# FPGA_I2C.net
KiCad netlist of a schematic drawn in Altium Designer
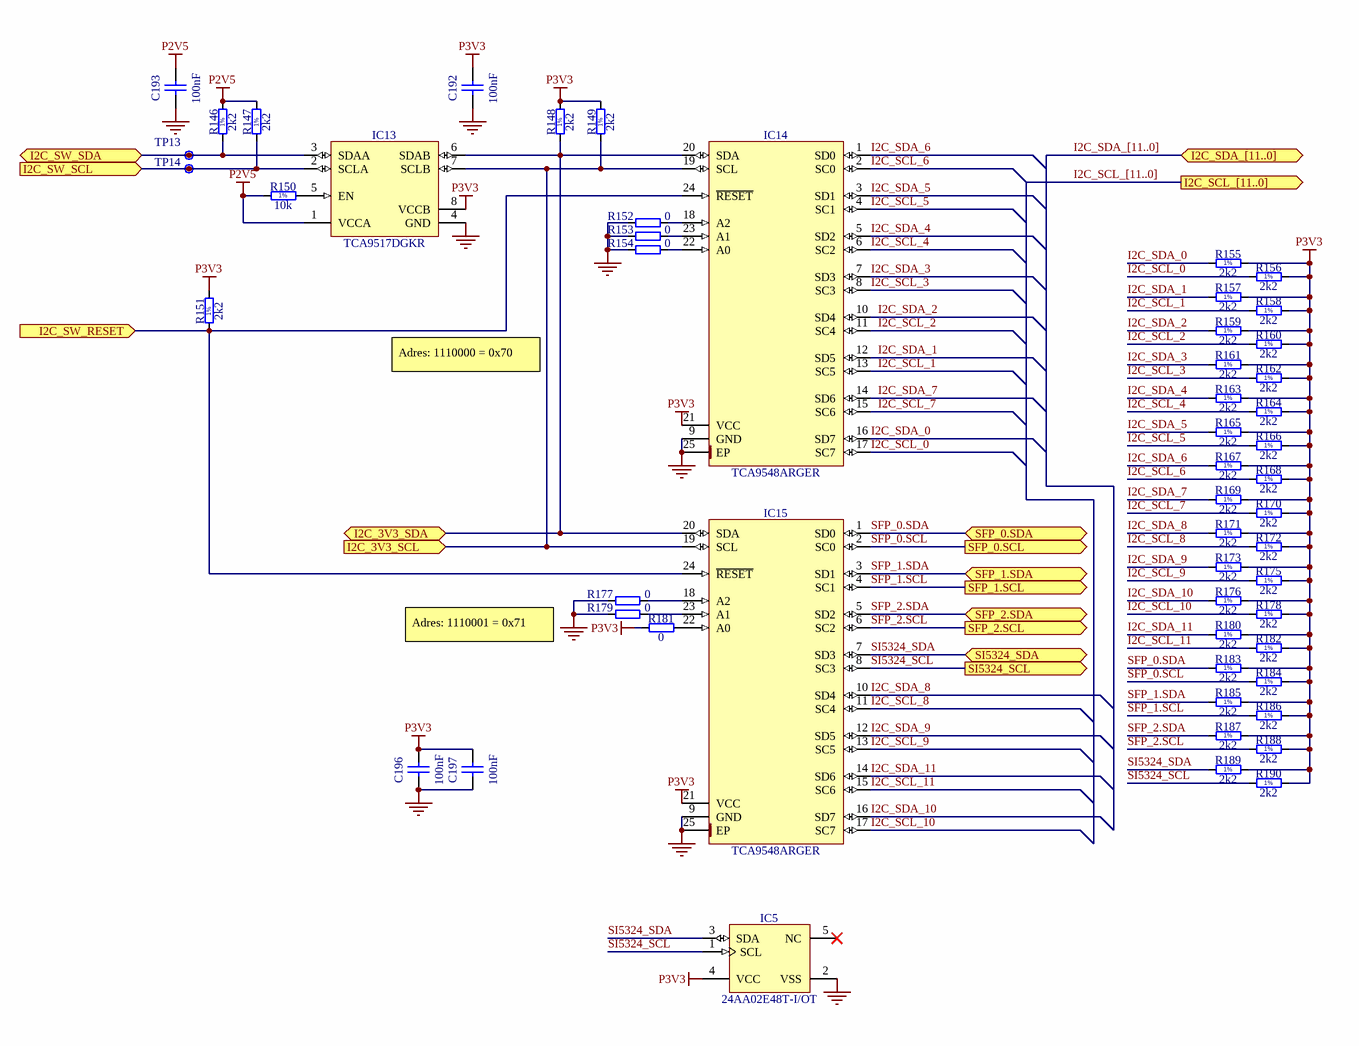
[diagram p0: FPGA_I2C.SchDoc]

(export (version "E")
  (design (tool "Eeschema 10.0.6"))
  (components
    (comp (ref "C192")
      (value "100nF")
      (footprint "CAPC0603X33N")
      (description "Non-polarised capacitor")
      (fields
        (field (name "PART NUMBER") "CC0201_100NF_6.3V_10%_X5R")
        (field (name "VOLTAGE") "6.3V")
        (field (name "AUTHOR") "CERN DEM JLC")
      )
      (libsource (lib "Capacitors") (part "Capacitor - non polarized"))
    )
    (comp (ref "C193")
      (value "100nF")
      (footprint "CAPC0603X33N")
      (description "Non-polarised capacitor")
      (fields
        (field (name "PART NUMBER") "CC0201_100NF_6.3V_10%_X5R")
        (field (name "VOLTAGE") "6.3V")
        (field (name "AUTHOR") "CERN DEM JLC")
      )
      (libsource (lib "Capacitors") (part "Capacitor - non polarized"))
    )
    (comp (ref "C196")
      (value "100nF")
      (footprint "CAPC0603X33N")
      (description "Non-polarised capacitor")
      (fields
        (field (name "PART NUMBER") "CC0201_100NF_6.3V_10%_X5R")
        (field (name "VOLTAGE") "6.3V")
        (field (name "AUTHOR") "CERN DEM JLC")
      )
      (libsource (lib "Capacitors") (part "Capacitor - non polarized"))
    )
    (comp (ref "C197")
      (value "100nF")
      (footprint "CAPC0603X33N")
      (description "Non-polarised capacitor")
      (fields
        (field (name "PART NUMBER") "CC0201_100NF_6.3V_10%_X5R")
        (field (name "VOLTAGE") "6.3V")
        (field (name "AUTHOR") "CERN DEM JLC")
      )
      (libsource (lib "Capacitors") (part "Capacitor - non polarized"))
    )
    (comp (ref "IC5")
      (value "24AA02E48T-I/OT")
      (footprint "SOT95P280X145-5N")
      (description "1.7V-5.5V, 2K I2C Serial EEPROM With EUI-48 Node Identity")
      (fields (field (name "MANUFACTURER") "MICROCHIP TECHNOLOGY") (field (name "AUTHOR") "CERN DEM MR"))
      (libsource (lib "ICs And Semiconductors") (part "24AA02E48T-I/OT"))
    )
    (comp (ref "IC13")
      (value "TCA9517DGKR")
      (footprint "SOP65P490X110-8N")
      (description "Level-Translating I2C Bus Repeater")
      (fields (field (name "MANUFACTURER") "TEXAS INSTRUMENTS") (field (name "AUTHOR") "CERN DEM JLC"))
      (libsource (lib "ICs And Semiconductors") (part "TCA9517"))
    )
    (comp (ref "IC14")
      (value "TCA9548ARGER")
      (footprint "QFN50P400X400X100-25N-S220")
      (description "Low Voltage 8-Channel I2C Switch With Reset")
      (fields (field (name "MANUFACTURER") "TEXAS INSTRUMENTS") (field (name "AUTHOR") "CERN DEM JLC"))
      (libsource (lib "ICs And Semiconductors") (part "TCA9548ARGER"))
    )
    (comp (ref "IC15")
      (value "TCA9548ARGER")
      (footprint "QFN50P400X400X100-25N-S220")
      (description "Low Voltage 8-Channel I2C Switch With Reset")
      (fields (field (name "MANUFACTURER") "TEXAS INSTRUMENTS") (field (name "AUTHOR") "CERN DEM JLC"))
      (libsource (lib "ICs And Semiconductors") (part "TCA9548ARGER"))
    )
    (comp (ref "R146")
      (value "2k2")
      (footprint "RESC1005X40N")
      (description "Resistor - 1%")
      (fields
        (field (name "PART NUMBER") "R0402_2K2_1%_0.0625W_100PPM")
        (field (name "POWER") "0.0625W")
        (field (name "AUTHOR") "CERN DEM JLC")
      )
      (libsource (lib "Resistors") (part "Resistor - 1%"))
    )
    (comp (ref "R147")
      (value "2k2")
      (footprint "RESC1005X40N")
      (description "Resistor - 1%")
      (fields
        (field (name "PART NUMBER") "R0402_2K2_1%_0.0625W_100PPM")
        (field (name "POWER") "0.0625W")
        (field (name "AUTHOR") "CERN DEM JLC")
      )
      (libsource (lib "Resistors") (part "Resistor - 1%"))
    )
    (comp (ref "R148")
      (value "2k2")
      (footprint "RESC1005X40N")
      (description "Resistor - 1%")
      (fields
        (field (name "PART NUMBER") "R0402_2K2_1%_0.0625W_100PPM")
        (field (name "POWER") "0.0625W")
        (field (name "AUTHOR") "CERN DEM JLC")
      )
      (libsource (lib "Resistors") (part "Resistor - 1%"))
    )
    (comp (ref "R149")
      (value "2k2")
      (footprint "RESC1005X40N")
      (description "Resistor - 1%")
      (fields
        (field (name "PART NUMBER") "R0402_2K2_1%_0.0625W_100PPM")
        (field (name "POWER") "0.0625W")
        (field (name "AUTHOR") "CERN DEM JLC")
      )
      (libsource (lib "Resistors") (part "Resistor - 1%"))
    )
    (comp (ref "R150")
      (value "10k")
      (footprint "RESC1005X40N")
      (description "Resistor - 1%")
      (fields
        (field (name "PART NUMBER") "R0402_10K_1%_0.0625W_100PPM")
        (field (name "POWER") "0.0625W")
        (field (name "AUTHOR") "CERN DEM JLC")
      )
      (libsource (lib "Resistors") (part "Resistor - 1%"))
    )
    (comp (ref "R151")
      (value "2k2")
      (footprint "RESC1005X40N")
      (description "Resistor - 1%")
      (fields
        (field (name "PART NUMBER") "R0402_2K2_1%_0.0625W_100PPM")
        (field (name "POWER") "0.0625W")
        (field (name "AUTHOR") "CERN DEM JLC")
      )
      (libsource (lib "Resistors") (part "Resistor - 1%"))
    )
    (comp (ref "R152")
      (value "0")
      (footprint "RESC1005X40N")
      (description "Resistor")
      (fields
        (field (name "PART NUMBER") "R0402_0R_JUMPER")
        (field (name "MANUFACTURER") "GENERIC")
        (field (name "AUTHOR") "CERN DEM JLC")
      )
      (libsource (lib "Resistors") (part "Resistor"))
    )
    (comp (ref "R153")
      (value "0")
      (footprint "RESC1005X40N")
      (description "Resistor")
      (fields
        (field (name "PART NUMBER") "R0402_0R_JUMPER")
        (field (name "MANUFACTURER") "GENERIC")
        (field (name "AUTHOR") "CERN DEM JLC")
      )
      (libsource (lib "Resistors") (part "Resistor"))
    )
    (comp (ref "R154")
      (value "0")
      (footprint "RESC1005X40N")
      (description "Resistor")
      (fields
        (field (name "PART NUMBER") "R0402_0R_JUMPER")
        (field (name "MANUFACTURER") "GENERIC")
        (field (name "AUTHOR") "CERN DEM JLC")
      )
      (libsource (lib "Resistors") (part "Resistor"))
    )
    (comp (ref "R155")
      (value "2k2")
      (footprint "RESC1005X40N")
      (description "Resistor - 1%")
      (fields
        (field (name "PART NUMBER") "R0402_2K2_1%_0.0625W_100PPM")
        (field (name "POWER") "0.0625W")
        (field (name "AUTHOR") "CERN DEM JLC")
      )
      (libsource (lib "Resistors") (part "Resistor - 1%"))
    )
    (comp (ref "R156")
      (value "2k2")
      (footprint "RESC1005X40N")
      (description "Resistor - 1%")
      (fields
        (field (name "PART NUMBER") "R0402_2K2_1%_0.0625W_100PPM")
        (field (name "POWER") "0.0625W")
        (field (name "AUTHOR") "CERN DEM JLC")
      )
      (libsource (lib "Resistors") (part "Resistor - 1%"))
    )
    (comp (ref "R157")
      (value "2k2")
      (footprint "RESC1005X40N")
      (description "Resistor - 1%")
      (fields
        (field (name "PART NUMBER") "R0402_2K2_1%_0.0625W_100PPM")
        (field (name "POWER") "0.0625W")
        (field (name "AUTHOR") "CERN DEM JLC")
      )
      (libsource (lib "Resistors") (part "Resistor - 1%"))
    )
    (comp (ref "R158")
      (value "2k2")
      (footprint "RESC1005X40N")
      (description "Resistor - 1%")
      (fields
        (field (name "PART NUMBER") "R0402_2K2_1%_0.0625W_100PPM")
        (field (name "POWER") "0.0625W")
        (field (name "AUTHOR") "CERN DEM JLC")
      )
      (libsource (lib "Resistors") (part "Resistor - 1%"))
    )
    (comp (ref "R159")
      (value "2k2")
      (footprint "RESC1005X40N")
      (description "Resistor - 1%")
      (fields
        (field (name "PART NUMBER") "R0402_2K2_1%_0.0625W_100PPM")
        (field (name "POWER") "0.0625W")
        (field (name "AUTHOR") "CERN DEM JLC")
      )
      (libsource (lib "Resistors") (part "Resistor - 1%"))
    )
    (comp (ref "R160")
      (value "2k2")
      (footprint "RESC1005X40N")
      (description "Resistor - 1%")
      (fields
        (field (name "PART NUMBER") "R0402_2K2_1%_0.0625W_100PPM")
        (field (name "POWER") "0.0625W")
        (field (name "AUTHOR") "CERN DEM JLC")
      )
      (libsource (lib "Resistors") (part "Resistor - 1%"))
    )
    (comp (ref "R161")
      (value "2k2")
      (footprint "RESC1005X40N")
      (description "Resistor - 1%")
      (fields
        (field (name "PART NUMBER") "R0402_2K2_1%_0.0625W_100PPM")
        (field (name "POWER") "0.0625W")
        (field (name "AUTHOR") "CERN DEM JLC")
      )
      (libsource (lib "Resistors") (part "Resistor - 1%"))
    )
    (comp (ref "R162")
      (value "2k2")
      (footprint "RESC1005X40N")
      (description "Resistor - 1%")
      (fields
        (field (name "PART NUMBER") "R0402_2K2_1%_0.0625W_100PPM")
        (field (name "POWER") "0.0625W")
        (field (name "AUTHOR") "CERN DEM JLC")
      )
      (libsource (lib "Resistors") (part "Resistor - 1%"))
    )
    (comp (ref "R163")
      (value "2k2")
      (footprint "RESC1005X40N")
      (description "Resistor - 1%")
      (fields
        (field (name "PART NUMBER") "R0402_2K2_1%_0.0625W_100PPM")
        (field (name "POWER") "0.0625W")
        (field (name "AUTHOR") "CERN DEM JLC")
      )
      (libsource (lib "Resistors") (part "Resistor - 1%"))
    )
    (comp (ref "R164")
      (value "2k2")
      (footprint "RESC1005X40N")
      (description "Resistor - 1%")
      (fields
        (field (name "PART NUMBER") "R0402_2K2_1%_0.0625W_100PPM")
        (field (name "POWER") "0.0625W")
        (field (name "AUTHOR") "CERN DEM JLC")
      )
      (libsource (lib "Resistors") (part "Resistor - 1%"))
    )
    (comp (ref "R165")
      (value "2k2")
      (footprint "RESC1005X40N")
      (description "Resistor - 1%")
      (fields
        (field (name "PART NUMBER") "R0402_2K2_1%_0.0625W_100PPM")
        (field (name "POWER") "0.0625W")
        (field (name "AUTHOR") "CERN DEM JLC")
      )
      (libsource (lib "Resistors") (part "Resistor - 1%"))
    )
    (comp (ref "R166")
      (value "2k2")
      (footprint "RESC1005X40N")
      (description "Resistor - 1%")
      (fields
        (field (name "PART NUMBER") "R0402_2K2_1%_0.0625W_100PPM")
        (field (name "POWER") "0.0625W")
        (field (name "AUTHOR") "CERN DEM JLC")
      )
      (libsource (lib "Resistors") (part "Resistor - 1%"))
    )
    (comp (ref "R167")
      (value "2k2")
      (footprint "RESC1005X40N")
      (description "Resistor - 1%")
      (fields
        (field (name "PART NUMBER") "R0402_2K2_1%_0.0625W_100PPM")
        (field (name "POWER") "0.0625W")
        (field (name "AUTHOR") "CERN DEM JLC")
      )
      (libsource (lib "Resistors") (part "Resistor - 1%"))
    )
    (comp (ref "R168")
      (value "2k2")
      (footprint "RESC1005X40N")
      (description "Resistor - 1%")
      (fields
        (field (name "PART NUMBER") "R0402_2K2_1%_0.0625W_100PPM")
        (field (name "POWER") "0.0625W")
        (field (name "AUTHOR") "CERN DEM JLC")
      )
      (libsource (lib "Resistors") (part "Resistor - 1%"))
    )
    (comp (ref "R169")
      (value "2k2")
      (footprint "RESC1005X40N")
      (description "Resistor - 1%")
      (fields
        (field (name "PART NUMBER") "R0402_2K2_1%_0.0625W_100PPM")
        (field (name "POWER") "0.0625W")
        (field (name "AUTHOR") "CERN DEM JLC")
      )
      (libsource (lib "Resistors") (part "Resistor - 1%"))
    )
    (comp (ref "R170")
      (value "2k2")
      (footprint "RESC1005X40N")
      (description "Resistor - 1%")
      (fields
        (field (name "PART NUMBER") "R0402_2K2_1%_0.0625W_100PPM")
        (field (name "POWER") "0.0625W")
        (field (name "AUTHOR") "CERN DEM JLC")
      )
      (libsource (lib "Resistors") (part "Resistor - 1%"))
    )
    (comp (ref "R171")
      (value "2k2")
      (footprint "RESC1005X40N")
      (description "Resistor - 1%")
      (fields
        (field (name "PART NUMBER") "R0402_2K2_1%_0.0625W_100PPM")
        (field (name "POWER") "0.0625W")
        (field (name "AUTHOR") "CERN DEM JLC")
      )
      (libsource (lib "Resistors") (part "Resistor - 1%"))
    )
    (comp (ref "R172")
      (value "2k2")
      (footprint "RESC1005X40N")
      (description "Resistor - 1%")
      (fields
        (field (name "PART NUMBER") "R0402_2K2_1%_0.0625W_100PPM")
        (field (name "POWER") "0.0625W")
        (field (name "AUTHOR") "CERN DEM JLC")
      )
      (libsource (lib "Resistors") (part "Resistor - 1%"))
    )
    (comp (ref "R173")
      (value "2k2")
      (footprint "RESC1005X40N")
      (description "Resistor - 1%")
      (fields
        (field (name "PART NUMBER") "R0402_2K2_1%_0.0625W_100PPM")
        (field (name "POWER") "0.0625W")
        (field (name "AUTHOR") "CERN DEM JLC")
      )
      (libsource (lib "Resistors") (part "Resistor - 1%"))
    )
    (comp (ref "R175")
      (value "2k2")
      (footprint "RESC1005X40N")
      (description "Resistor - 1%")
      (fields
        (field (name "PART NUMBER") "R0402_2K2_1%_0.0625W_100PPM")
        (field (name "POWER") "0.0625W")
        (field (name "AUTHOR") "CERN DEM JLC")
      )
      (libsource (lib "Resistors") (part "Resistor - 1%"))
    )
    (comp (ref "R176")
      (value "2k2")
      (footprint "RESC1005X40N")
      (description "Resistor - 1%")
      (fields
        (field (name "PART NUMBER") "R0402_2K2_1%_0.0625W_100PPM")
        (field (name "POWER") "0.0625W")
        (field (name "AUTHOR") "CERN DEM JLC")
      )
      (libsource (lib "Resistors") (part "Resistor - 1%"))
    )
    (comp (ref "R177")
      (value "0")
      (footprint "RESC1005X40N")
      (description "Resistor")
      (fields
        (field (name "PART NUMBER") "R0402_0R_JUMPER")
        (field (name "MANUFACTURER") "GENERIC")
        (field (name "AUTHOR") "CERN DEM JLC")
      )
      (libsource (lib "Resistors") (part "Resistor"))
    )
    (comp (ref "R178")
      (value "2k2")
      (footprint "RESC1005X40N")
      (description "Resistor - 1%")
      (fields
        (field (name "PART NUMBER") "R0402_2K2_1%_0.0625W_100PPM")
        (field (name "POWER") "0.0625W")
        (field (name "AUTHOR") "CERN DEM JLC")
      )
      (libsource (lib "Resistors") (part "Resistor - 1%"))
    )
    (comp (ref "R179")
      (value "0")
      (footprint "RESC1005X40N")
      (description "Resistor")
      (fields
        (field (name "PART NUMBER") "R0402_0R_JUMPER")
        (field (name "MANUFACTURER") "GENERIC")
        (field (name "AUTHOR") "CERN DEM JLC")
      )
      (libsource (lib "Resistors") (part "Resistor"))
    )
    (comp (ref "R180")
      (value "2k2")
      (footprint "RESC1005X40N")
      (description "Resistor - 1%")
      (fields
        (field (name "PART NUMBER") "R0402_2K2_1%_0.0625W_100PPM")
        (field (name "POWER") "0.0625W")
        (field (name "AUTHOR") "CERN DEM JLC")
      )
      (libsource (lib "Resistors") (part "Resistor - 1%"))
    )
    (comp (ref "R181")
      (value "0")
      (footprint "RESC1005X40N")
      (description "Resistor")
      (fields
        (field (name "PART NUMBER") "R0402_0R_JUMPER")
        (field (name "MANUFACTURER") "GENERIC")
        (field (name "AUTHOR") "CERN DEM JLC")
      )
      (libsource (lib "Resistors") (part "Resistor"))
    )
    (comp (ref "R182")
      (value "2k2")
      (footprint "RESC1005X40N")
      (description "Resistor - 1%")
      (fields
        (field (name "PART NUMBER") "R0402_2K2_1%_0.0625W_100PPM")
        (field (name "POWER") "0.0625W")
        (field (name "AUTHOR") "CERN DEM JLC")
      )
      (libsource (lib "Resistors") (part "Resistor - 1%"))
    )
    (comp (ref "R183")
      (value "2k2")
      (footprint "RESC1005X40N")
      (description "Resistor - 1%")
      (fields
        (field (name "PART NUMBER") "R0402_2K2_1%_0.0625W_100PPM")
        (field (name "POWER") "0.0625W")
        (field (name "AUTHOR") "CERN DEM JLC")
      )
      (libsource (lib "Resistors") (part "Resistor - 1%"))
    )
    (comp (ref "R184")
      (value "2k2")
      (footprint "RESC1005X40N")
      (description "Resistor - 1%")
      (fields
        (field (name "PART NUMBER") "R0402_2K2_1%_0.0625W_100PPM")
        (field (name "POWER") "0.0625W")
        (field (name "AUTHOR") "CERN DEM JLC")
      )
      (libsource (lib "Resistors") (part "Resistor - 1%"))
    )
    (comp (ref "R185")
      (value "2k2")
      (footprint "RESC1005X40N")
      (description "Resistor - 1%")
      (fields
        (field (name "PART NUMBER") "R0402_2K2_1%_0.0625W_100PPM")
        (field (name "POWER") "0.0625W")
        (field (name "AUTHOR") "CERN DEM JLC")
      )
      (libsource (lib "Resistors") (part "Resistor - 1%"))
    )
    (comp (ref "R186")
      (value "2k2")
      (footprint "RESC1005X40N")
      (description "Resistor - 1%")
      (fields
        (field (name "PART NUMBER") "R0402_2K2_1%_0.0625W_100PPM")
        (field (name "POWER") "0.0625W")
        (field (name "AUTHOR") "CERN DEM JLC")
      )
      (libsource (lib "Resistors") (part "Resistor - 1%"))
    )
    (comp (ref "R187")
      (value "2k2")
      (footprint "RESC1005X40N")
      (description "Resistor - 1%")
      (fields
        (field (name "PART NUMBER") "R0402_2K2_1%_0.0625W_100PPM")
        (field (name "POWER") "0.0625W")
        (field (name "AUTHOR") "CERN DEM JLC")
      )
      (libsource (lib "Resistors") (part "Resistor - 1%"))
    )
    (comp (ref "R188")
      (value "2k2")
      (footprint "RESC1005X40N")
      (description "Resistor - 1%")
      (fields
        (field (name "PART NUMBER") "R0402_2K2_1%_0.0625W_100PPM")
        (field (name "POWER") "0.0625W")
        (field (name "AUTHOR") "CERN DEM JLC")
      )
      (libsource (lib "Resistors") (part "Resistor - 1%"))
    )
    (comp (ref "R189")
      (value "2k2")
      (footprint "RESC1005X40N")
      (description "Resistor - 1%")
      (fields
        (field (name "PART NUMBER") "R0402_2K2_1%_0.0625W_100PPM")
        (field (name "POWER") "0.0625W")
        (field (name "AUTHOR") "CERN DEM JLC")
      )
      (libsource (lib "Resistors") (part "Resistor - 1%"))
    )
    (comp (ref "R190")
      (value "2k2")
      (footprint "RESC1005X40N")
      (description "Resistor - 1%")
      (fields
        (field (name "PART NUMBER") "R0402_2K2_1%_0.0625W_100PPM")
        (field (name "POWER") "0.0625W")
        (field (name "AUTHOR") "CERN DEM JLC")
      )
      (libsource (lib "Resistors") (part "Resistor - 1%"))
    )
    (comp (ref "TP13")
      (value "I2C SW SDA")
      (footprint "TPS127")
      (description "Test Point")
      (fields (field (name "PART NUMBER") "SMD_PAD_1.27X1.27MM") (field (name "AUTHOR") "CERN DEM JLC"))
      (libsource (lib "Eletro-mechanical") (part "Test Point"))
    )
    (comp (ref "TP14")
      (value "I2C SW SCL")
      (footprint "TPS127")
      (description "Test Point")
      (fields (field (name "PART NUMBER") "SMD_PAD_1.27X1.27MM") (field (name "AUTHOR") "CERN DEM JLC"))
      (libsource (lib "Eletro-mechanical") (part "Test Point"))
    )
  )
  (nets
    (net (code "1") (name "/I2C_3V3_SCL") (class "Default")
      (node (ref "IC13") (pin "7") (pinfunction "SCLB_7") (pintype "bidirectional"))
      (node (ref "IC14") (pin "19") (pinfunction "SCL_19") (pintype "bidirectional"))
      (node (ref "IC15") (pin "19") (pinfunction "SCL_19") (pintype "bidirectional"))
      (node (ref "R149") (pin "1") (pinfunction "1_1") (pintype "passive"))
    )
    (net (code "2") (name "/I2C_3V3_SDA") (class "Default")
      (node (ref "IC13") (pin "6") (pinfunction "SDAB_6") (pintype "bidirectional"))
      (node (ref "IC14") (pin "20") (pinfunction "SDA_20") (pintype "bidirectional"))
      (node (ref "IC15") (pin "20") (pinfunction "SDA_20") (pintype "bidirectional"))
      (node (ref "R148") (pin "1") (pinfunction "1_1") (pintype "passive"))
    )
    (net (code "3") (name "/I2C_SCL_0") (class "Default")
      (node (ref "IC14") (pin "17") (pinfunction "SC7_17") (pintype "bidirectional"))
      (node (ref "R156") (pin "1") (pinfunction "1_1") (pintype "passive"))
    )
    (net (code "4") (name "/I2C_SCL_1") (class "Default")
      (node (ref "IC14") (pin "13") (pinfunction "SC5_13") (pintype "bidirectional"))
      (node (ref "R158") (pin "1") (pinfunction "1_1") (pintype "passive"))
    )
    (net (code "5") (name "/I2C_SCL_2") (class "Default")
      (node (ref "IC14") (pin "11") (pinfunction "SC4_11") (pintype "bidirectional"))
      (node (ref "R160") (pin "1") (pinfunction "1_1") (pintype "passive"))
    )
    (net (code "6") (name "/I2C_SCL_3") (class "Default")
      (node (ref "IC14") (pin "8") (pinfunction "SC3_8") (pintype "bidirectional"))
      (node (ref "R162") (pin "1") (pinfunction "1_1") (pintype "passive"))
    )
    (net (code "7") (name "/I2C_SCL_4") (class "Default")
      (node (ref "IC14") (pin "6") (pinfunction "SC2_6") (pintype "bidirectional"))
      (node (ref "R164") (pin "1") (pinfunction "1_1") (pintype "passive"))
    )
    (net (code "8") (name "/I2C_SCL_5") (class "Default")
      (node (ref "IC14") (pin "4") (pinfunction "SC1_4") (pintype "bidirectional"))
      (node (ref "R166") (pin "1") (pinfunction "1_1") (pintype "passive"))
    )
    (net (code "9") (name "/I2C_SCL_6") (class "Default")
      (node (ref "IC14") (pin "2") (pinfunction "SC0_2") (pintype "bidirectional"))
      (node (ref "R168") (pin "1") (pinfunction "1_1") (pintype "passive"))
    )
    (net (code "10") (name "/I2C_SCL_7") (class "Default")
      (node (ref "IC14") (pin "15") (pinfunction "SC6_15") (pintype "bidirectional"))
      (node (ref "R170") (pin "1") (pinfunction "1_1") (pintype "passive"))
    )
    (net (code "11") (name "/I2C_SCL_8") (class "Default")
      (node (ref "IC15") (pin "11") (pinfunction "SC4_11") (pintype "bidirectional"))
      (node (ref "R172") (pin "1") (pinfunction "1_1") (pintype "passive"))
    )
    (net (code "12") (name "/I2C_SCL_9") (class "Default")
      (node (ref "IC15") (pin "13") (pinfunction "SC5_13") (pintype "bidirectional"))
      (node (ref "R175") (pin "1") (pinfunction "1_1") (pintype "passive"))
    )
    (net (code "13") (name "/I2C_SCL_10") (class "Default")
      (node (ref "IC15") (pin "17") (pinfunction "SC7_17") (pintype "bidirectional"))
      (node (ref "R178") (pin "1") (pinfunction "1_1") (pintype "passive"))
    )
    (net (code "14") (name "/I2C_SCL_11") (class "Default")
      (node (ref "IC15") (pin "15") (pinfunction "SC6_15") (pintype "bidirectional"))
      (node (ref "R182") (pin "1") (pinfunction "1_1") (pintype "passive"))
    )
    (net (code "16") (name "/I2C_SDA_0") (class "Default")
      (node (ref "IC14") (pin "16") (pinfunction "SD7_16") (pintype "bidirectional"))
      (node (ref "R155") (pin "1") (pinfunction "1_1") (pintype "passive"))
    )
    (net (code "17") (name "/I2C_SDA_1") (class "Default")
      (node (ref "IC14") (pin "12") (pinfunction "SD5_12") (pintype "bidirectional"))
      (node (ref "R157") (pin "1") (pinfunction "1_1") (pintype "passive"))
    )
    (net (code "18") (name "/I2C_SDA_2") (class "Default")
      (node (ref "IC14") (pin "10") (pinfunction "SD4_10") (pintype "bidirectional"))
      (node (ref "R159") (pin "1") (pinfunction "1_1") (pintype "passive"))
    )
    (net (code "19") (name "/I2C_SDA_3") (class "Default")
      (node (ref "IC14") (pin "7") (pinfunction "SD3_7") (pintype "bidirectional"))
      (node (ref "R161") (pin "1") (pinfunction "1_1") (pintype "passive"))
    )
    (net (code "20") (name "/I2C_SDA_4") (class "Default")
      (node (ref "IC14") (pin "5") (pinfunction "SD2_5") (pintype "bidirectional"))
      (node (ref "R163") (pin "1") (pinfunction "1_1") (pintype "passive"))
    )
    (net (code "21") (name "/I2C_SDA_5") (class "Default")
      (node (ref "IC14") (pin "3") (pinfunction "SD1_3") (pintype "bidirectional"))
      (node (ref "R165") (pin "1") (pinfunction "1_1") (pintype "passive"))
    )
    (net (code "22") (name "/I2C_SDA_6") (class "Default")
      (node (ref "IC14") (pin "1") (pinfunction "SD0_1") (pintype "bidirectional"))
      (node (ref "R167") (pin "1") (pinfunction "1_1") (pintype "passive"))
    )
    (net (code "23") (name "/I2C_SDA_7") (class "Default")
      (node (ref "IC14") (pin "14") (pinfunction "SD6_14") (pintype "bidirectional"))
      (node (ref "R169") (pin "1") (pinfunction "1_1") (pintype "passive"))
    )
    (net (code "24") (name "/I2C_SDA_8") (class "Default")
      (node (ref "IC15") (pin "10") (pinfunction "SD4_10") (pintype "bidirectional"))
      (node (ref "R171") (pin "1") (pinfunction "1_1") (pintype "passive"))
    )
    (net (code "25") (name "/I2C_SDA_9") (class "Default")
      (node (ref "IC15") (pin "12") (pinfunction "SD5_12") (pintype "bidirectional"))
      (node (ref "R173") (pin "1") (pinfunction "1_1") (pintype "passive"))
    )
    (net (code "26") (name "/I2C_SDA_10") (class "Default")
      (node (ref "IC15") (pin "16") (pinfunction "SD7_16") (pintype "bidirectional"))
      (node (ref "R176") (pin "1") (pinfunction "1_1") (pintype "passive"))
    )
    (net (code "27") (name "/I2C_SDA_11") (class "Default")
      (node (ref "IC15") (pin "14") (pinfunction "SD6_14") (pintype "bidirectional"))
      (node (ref "R180") (pin "1") (pinfunction "1_1") (pintype "passive"))
    )
    (net (code "29") (name "/I2C_SW_RESET") (class "Default")
      (node (ref "IC14") (pin "24") (pinfunction "~{RESET}_24") (pintype "input"))
      (node (ref "IC15") (pin "24") (pinfunction "~{RESET}_24") (pintype "input"))
      (node (ref "R151") (pin "1") (pinfunction "1_1") (pintype "passive"))
    )
    (net (code "30") (name "/I2C_SW_SCL") (class "Default")
      (node (ref "IC13") (pin "2") (pinfunction "SCLA_2") (pintype "bidirectional"))
      (node (ref "R147") (pin "1") (pinfunction "1_1") (pintype "passive"))
      (node (ref "TP14") (pin "1") (pinfunction "1_1") (pintype "bidirectional"))
    )
    (net (code "31") (name "/I2C_SW_SDA") (class "Default")
      (node (ref "IC13") (pin "3") (pinfunction "SDAA_3") (pintype "bidirectional"))
      (node (ref "R146") (pin "1") (pinfunction "1_1") (pintype "passive"))
      (node (ref "TP13") (pin "1") (pinfunction "1_1") (pintype "bidirectional"))
    )
    (net (code "32") (name "/SFP_0.SCL") (class "Default")
      (node (ref "IC15") (pin "2") (pinfunction "SC0_2") (pintype "bidirectional"))
      (node (ref "R184") (pin "1") (pinfunction "1_1") (pintype "passive"))
    )
    (net (code "33") (name "/SFP_0.SDA") (class "Default")
      (node (ref "IC15") (pin "1") (pinfunction "SD0_1") (pintype "bidirectional"))
      (node (ref "R183") (pin "1") (pinfunction "1_1") (pintype "passive"))
    )
    (net (code "34") (name "/SFP_1.SCL") (class "Default")
      (node (ref "IC15") (pin "4") (pinfunction "SC1_4") (pintype "bidirectional"))
      (node (ref "R186") (pin "1") (pinfunction "1_1") (pintype "passive"))
    )
    (net (code "35") (name "/SFP_1.SDA") (class "Default")
      (node (ref "IC15") (pin "3") (pinfunction "SD1_3") (pintype "bidirectional"))
      (node (ref "R185") (pin "1") (pinfunction "1_1") (pintype "passive"))
    )
    (net (code "36") (name "/SFP_2.SCL") (class "Default")
      (node (ref "IC15") (pin "6") (pinfunction "SC2_6") (pintype "bidirectional"))
      (node (ref "R188") (pin "1") (pinfunction "1_1") (pintype "passive"))
    )
    (net (code "37") (name "/SFP_2.SDA") (class "Default")
      (node (ref "IC15") (pin "5") (pinfunction "SD2_5") (pintype "bidirectional"))
      (node (ref "R187") (pin "1") (pinfunction "1_1") (pintype "passive"))
    )
    (net (code "38") (name "/SI5324_SCL") (class "Default")
      (node (ref "IC15") (pin "8") (pinfunction "SC3_8") (pintype "bidirectional"))
      (node (ref "IC5") (pin "1") (pinfunction "SCL_1") (pintype "input"))
      (node (ref "R190") (pin "1") (pinfunction "1_1") (pintype "passive"))
    )
    (net (code "39") (name "/SI5324_SDA") (class "Default")
      (node (ref "IC15") (pin "7") (pinfunction "SD3_7") (pintype "bidirectional"))
      (node (ref "IC5") (pin "3") (pinfunction "SDA_3") (pintype "bidirectional"))
      (node (ref "R189") (pin "1") (pinfunction "1_1") (pintype "passive"))
    )
    (net (code "40") (name "GND") (class "Default")
      (node (ref "C192") (pin "1") (pinfunction "1_1") (pintype "passive"))
      (node (ref "C193") (pin "1") (pinfunction "1_1") (pintype "passive"))
      (node (ref "C196") (pin "1") (pinfunction "1_1") (pintype "passive"))
      (node (ref "C197") (pin "1") (pinfunction "1_1") (pintype "passive"))
      (node (ref "IC13") (pin "4") (pinfunction "GND_4") (pintype "power_in"))
      (node (ref "IC14") (pin "25") (pinfunction "EP_25") (pintype "power_in"))
      (node (ref "IC14") (pin "9") (pinfunction "GND_9") (pintype "power_in"))
      (node (ref "IC15") (pin "25") (pinfunction "EP_25") (pintype "power_in"))
      (node (ref "IC15") (pin "9") (pinfunction "GND_9") (pintype "power_in"))
      (node (ref "IC5") (pin "2") (pinfunction "VSS_2") (pintype "power_in"))
      (node (ref "R152") (pin "1") (pinfunction "1_1") (pintype "passive"))
      (node (ref "R153") (pin "1") (pinfunction "1_1") (pintype "passive"))
      (node (ref "R154") (pin "1") (pinfunction "1_1") (pintype "passive"))
      (node (ref "R177") (pin "1") (pinfunction "1_1") (pintype "passive"))
      (node (ref "R179") (pin "1") (pinfunction "1_1") (pintype "passive"))
    )
    (net (code "41") (name "Net-(IC13-EN)") (class "Default")
      (node (ref "IC13") (pin "5") (pinfunction "EN_5") (pintype "input"))
      (node (ref "R150") (pin "2") (pinfunction "2_2") (pintype "passive"))
    )
    (net (code "42") (name "Net-(IC14-A0)") (class "Default")
      (node (ref "IC14") (pin "22") (pinfunction "A0_22") (pintype "input"))
      (node (ref "R154") (pin "2") (pinfunction "2_2") (pintype "passive"))
    )
    (net (code "43") (name "Net-(IC14-A1)") (class "Default")
      (node (ref "IC14") (pin "23") (pinfunction "A1_23") (pintype "input"))
      (node (ref "R153") (pin "2") (pinfunction "2_2") (pintype "passive"))
    )
    (net (code "44") (name "Net-(IC14-A2)") (class "Default")
      (node (ref "IC14") (pin "18") (pinfunction "A2_18") (pintype "input"))
      (node (ref "R152") (pin "2") (pinfunction "2_2") (pintype "passive"))
    )
    (net (code "45") (name "Net-(IC15-A0)") (class "Default")
      (node (ref "IC15") (pin "22") (pinfunction "A0_22") (pintype "input"))
      (node (ref "R181") (pin "2") (pinfunction "2_2") (pintype "passive"))
    )
    (net (code "46") (name "Net-(IC15-A1)") (class "Default")
      (node (ref "IC15") (pin "23") (pinfunction "A1_23") (pintype "input"))
      (node (ref "R179") (pin "2") (pinfunction "2_2") (pintype "passive"))
    )
    (net (code "47") (name "Net-(IC15-A2)") (class "Default")
      (node (ref "IC15") (pin "18") (pinfunction "A2_18") (pintype "input"))
      (node (ref "R177") (pin "2") (pinfunction "2_2") (pintype "passive"))
    )
    (net (code "48") (name "P2V5") (class "Default")
      (node (ref "C193") (pin "2") (pinfunction "2_2") (pintype "passive"))
      (node (ref "IC13") (pin "1") (pinfunction "VCCA_1") (pintype "power_in"))
      (node (ref "R146") (pin "2") (pinfunction "2_2") (pintype "passive"))
      (node (ref "R147") (pin "2") (pinfunction "2_2") (pintype "passive"))
      (node (ref "R150") (pin "1") (pinfunction "1_1") (pintype "passive"))
    )
    (net (code "49") (name "P3V3") (class "Default")
      (node (ref "C192") (pin "2") (pinfunction "2_2") (pintype "passive"))
      (node (ref "C196") (pin "2") (pinfunction "2_2") (pintype "passive"))
      (node (ref "C197") (pin "2") (pinfunction "2_2") (pintype "passive"))
      (node (ref "IC13") (pin "8") (pinfunction "VCCB_8") (pintype "power_in"))
      (node (ref "IC14") (pin "21") (pinfunction "VCC_21") (pintype "power_in"))
      (node (ref "IC15") (pin "21") (pinfunction "VCC_21") (pintype "power_in"))
      (node (ref "IC5") (pin "4") (pinfunction "VCC_4") (pintype "power_in"))
      (node (ref "R148") (pin "2") (pinfunction "2_2") (pintype "passive"))
      (node (ref "R149") (pin "2") (pinfunction "2_2") (pintype "passive"))
      (node (ref "R151") (pin "2") (pinfunction "2_2") (pintype "passive"))
      (node (ref "R155") (pin "2") (pinfunction "2_2") (pintype "passive"))
      (node (ref "R156") (pin "2") (pinfunction "2_2") (pintype "passive"))
      (node (ref "R157") (pin "2") (pinfunction "2_2") (pintype "passive"))
      (node (ref "R158") (pin "2") (pinfunction "2_2") (pintype "passive"))
      (node (ref "R159") (pin "2") (pinfunction "2_2") (pintype "passive"))
      (node (ref "R160") (pin "2") (pinfunction "2_2") (pintype "passive"))
      (node (ref "R161") (pin "2") (pinfunction "2_2") (pintype "passive"))
      (node (ref "R162") (pin "2") (pinfunction "2_2") (pintype "passive"))
      (node (ref "R163") (pin "2") (pinfunction "2_2") (pintype "passive"))
      (node (ref "R164") (pin "2") (pinfunction "2_2") (pintype "passive"))
      (node (ref "R165") (pin "2") (pinfunction "2_2") (pintype "passive"))
      (node (ref "R166") (pin "2") (pinfunction "2_2") (pintype "passive"))
      (node (ref "R167") (pin "2") (pinfunction "2_2") (pintype "passive"))
      (node (ref "R168") (pin "2") (pinfunction "2_2") (pintype "passive"))
      (node (ref "R169") (pin "2") (pinfunction "2_2") (pintype "passive"))
      (node (ref "R170") (pin "2") (pinfunction "2_2") (pintype "passive"))
      (node (ref "R171") (pin "2") (pinfunction "2_2") (pintype "passive"))
      (node (ref "R172") (pin "2") (pinfunction "2_2") (pintype "passive"))
      (node (ref "R173") (pin "2") (pinfunction "2_2") (pintype "passive"))
      (node (ref "R175") (pin "2") (pinfunction "2_2") (pintype "passive"))
      (node (ref "R176") (pin "2") (pinfunction "2_2") (pintype "passive"))
      (node (ref "R178") (pin "2") (pinfunction "2_2") (pintype "passive"))
      (node (ref "R180") (pin "2") (pinfunction "2_2") (pintype "passive"))
      (node (ref "R181") (pin "1") (pinfunction "1_1") (pintype "passive"))
      (node (ref "R182") (pin "2") (pinfunction "2_2") (pintype "passive"))
      (node (ref "R183") (pin "2") (pinfunction "2_2") (pintype "passive"))
      (node (ref "R184") (pin "2") (pinfunction "2_2") (pintype "passive"))
      (node (ref "R185") (pin "2") (pinfunction "2_2") (pintype "passive"))
      (node (ref "R186") (pin "2") (pinfunction "2_2") (pintype "passive"))
      (node (ref "R187") (pin "2") (pinfunction "2_2") (pintype "passive"))
      (node (ref "R188") (pin "2") (pinfunction "2_2") (pintype "passive"))
      (node (ref "R189") (pin "2") (pinfunction "2_2") (pintype "passive"))
      (node (ref "R190") (pin "2") (pinfunction "2_2") (pintype "passive"))
    )
    (net (code "50") (name "unconnected-(IC5-NC-Pad5)") (class "Default")
      (node (ref "IC5") (pin "5") (pinfunction "NC_5") (pintype "passive+no_connect"))
    )
  )
)
